# rapidshark-dart-detector-backlight-mk-1_.net
KiCad netlist of a schematic drawn in EAGLE
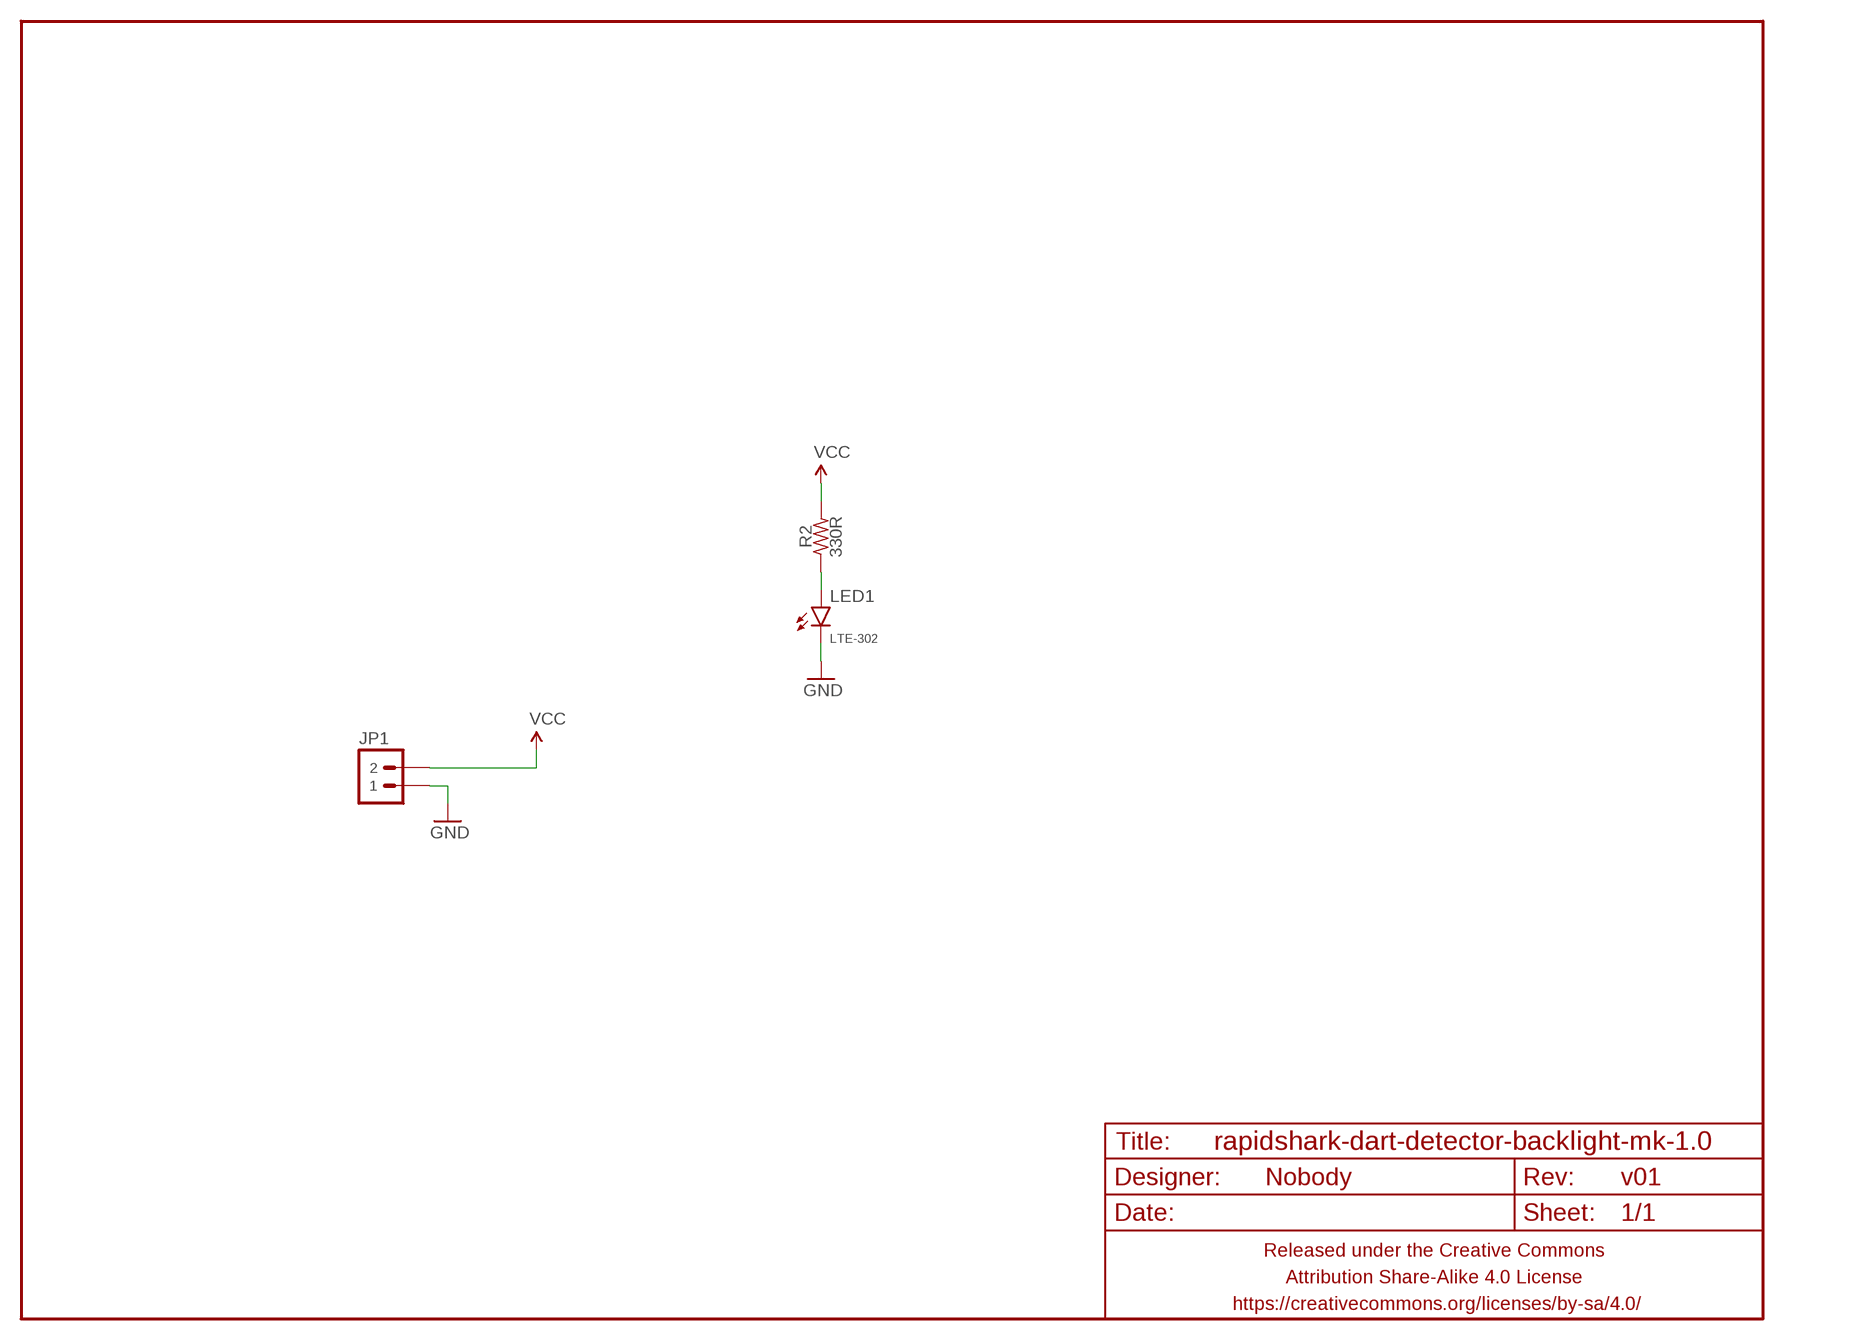
[diagram p0: schematic, sheet 1]

(export (version "E")
  (design (tool "Eeschema 10.0.6"))
  (components
    (comp (ref "FRAME1")
      (value "FRAME-LETTERNO_PACKAGE")
      (footprint "eagle-import:DUMMY")
      (fields (field (name "DESIGNER") "Nobody"))
      (libsource (lib "eagle-import") (part "FRAME-LETTERNO_PACKAGE"))
    )
    (comp (ref "JP1")
      (value "M02JST-PTH-RA-R+")
      (footprint "eagle-import:JST-2-PH-RA-PTH-R+")
      (libsource (lib "eagle-import") (part "M02JST-PTH-RA-R+"))
    )
    (comp (ref "LED1")
      (value "LTE-302")
      (footprint "eagle-import:LED-2.54MM-SIDE")
      (libsource (lib "eagle-import") (part "LED-VALUEIR-LED-SIDE"))
    )
    (comp (ref "R2")
      (value "330R")
      (footprint "eagle-import:RESISTOR-AXIAL-PTH-7.62MM")
      (libsource (lib "eagle-import") (part "RESISTORPTH-AXIAL-7.62MM"))
    )
  )
  (nets
    (net (code "1") (name "GND") (class "Default")
      (node (ref "JP1") (pin "1") (pinfunction "1_1") (pintype "passive"))
      (node (ref "LED1") (pin "K") (pinfunction "C_K") (pintype "passive"))
    )
    (net (code "2") (name "Net-(R2-1)") (class "Default")
      (node (ref "LED1") (pin "A") (pinfunction "A_A") (pintype "passive"))
      (node (ref "R2") (pin "P$1") (pinfunction "1_P$1") (pintype "passive"))
    )
    (net (code "3") (name "VCC") (class "Default")
      (node (ref "JP1") (pin "2") (pinfunction "2_2") (pintype "passive"))
      (node (ref "R2") (pin "P$2") (pinfunction "2_P$2") (pintype "passive"))
    )
  )
)
